# that2180_vca_new.net
KiCad netlist of a schematic drawn in EAGLE
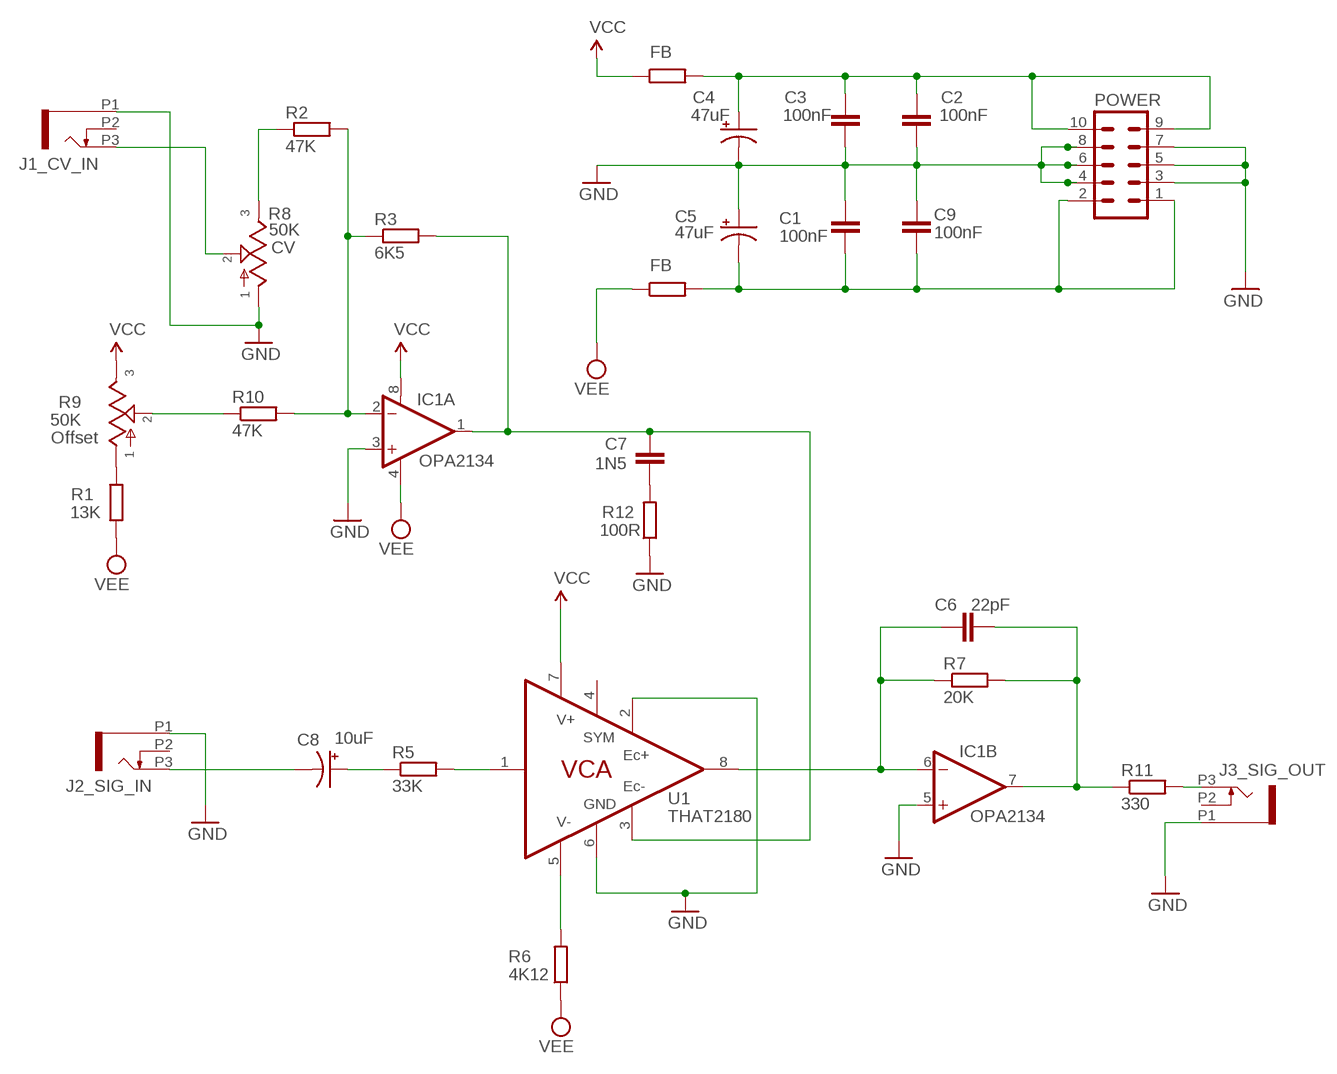
[diagram p0: schematic, sheet 1]

(export (version "E")
  (design (tool "Eeschema 10.0.6"))
  (components
    (comp (ref "C1")
      (value "100nF")
      (footprint "eagle-import:C050-025X075")
      (libsource (lib "eagle-import") (part "C-EU050-025X075"))
    )
    (comp (ref "C2")
      (value "100nF")
      (footprint "eagle-import:C050-025X075")
      (libsource (lib "eagle-import") (part "C-EU050-025X075"))
    )
    (comp (ref "C3")
      (value "100nF")
      (footprint "eagle-import:C050-025X075")
      (libsource (lib "eagle-import") (part "C-EU050-025X075"))
    )
    (comp (ref "C4")
      (value "47uF")
      (footprint "eagle-import:E2,5-5")
      (libsource (lib "eagle-import") (part "CPOL-USE2.5-5"))
    )
    (comp (ref "C5")
      (value "47uF")
      (footprint "eagle-import:E2,5-5")
      (libsource (lib "eagle-import") (part "CPOL-USE2.5-5"))
    )
    (comp (ref "C6")
      (value "22pF")
      (footprint "eagle-import:C050-025X075")
      (libsource (lib "eagle-import") (part "C-EU050-025X075"))
    )
    (comp (ref "C7")
      (value "1N5")
      (footprint "eagle-import:C050-025X075")
      (libsource (lib "eagle-import") (part "C-EU050-025X075"))
    )
    (comp (ref "C8")
      (value "10uF")
      (footprint "eagle-import:E2,5-5")
      (libsource (lib "eagle-import") (part "CPOL-USE2.5-5"))
    )
    (comp (ref "C9")
      (value "100nF")
      (footprint "eagle-import:C050-025X075")
      (libsource (lib "eagle-import") (part "C-EU050-025X075"))
    )
    (comp (ref "IC1")
      (value "OPAMP-DUALDIP")
      (footprint "eagle-import:DIP08")
      (libsource (lib "eagle-import") (part "OPAMP-DUALDIP"))
    )
    (comp (ref "J1_CV_IN")
      (value "PJ301_THONKICONN6")
      (footprint "eagle-import:WQP_PJ_301M6")
      (libsource (lib "eagle-import") (part "PJ301_THONKICONN6"))
    )
    (comp (ref "J2_SIG_IN")
      (value "PJ301_THONKICONN6")
      (footprint "eagle-import:WQP_PJ_301M6")
      (libsource (lib "eagle-import") (part "PJ301_THONKICONN6"))
    )
    (comp (ref "J3_SIG_OUT")
      (value "PJ301_THONKICONN6")
      (footprint "eagle-import:WQP_PJ_301M6")
      (libsource (lib "eagle-import") (part "PJ301_THONKICONN6"))
    )
    (comp (ref "POWER")
      (value "ML10")
      (footprint "eagle-import:ML10")
      (fields (field (name "OC_FARNELL") "unknown") (field (name "OC_NEWARK") "unknown"))
      (libsource (lib "eagle-import") (part "ML10"))
    )
    (comp (ref "R1")
      (value "13K")
      (footprint "eagle-import:0207_10")
      (libsource (lib "eagle-import") (part "R-EU_0207/10"))
    )
    (comp (ref "R2")
      (value "47K")
      (footprint "eagle-import:0207_10")
      (libsource (lib "eagle-import") (part "R-EU_0207/10"))
    )
    (comp (ref "R3")
      (value "6K5")
      (footprint "eagle-import:0207_10")
      (libsource (lib "eagle-import") (part "R-EU_0207/10"))
    )
    (comp (ref "R4")
      (value "FB")
      (footprint "eagle-import:0207_10")
      (libsource (lib "eagle-import") (part "R-EU_0207/10"))
    )
    (comp (ref "R5")
      (value "33K")
      (footprint "eagle-import:0207_10")
      (libsource (lib "eagle-import") (part "R-EU_0207/10"))
    )
    (comp (ref "R6")
      (value "4K12")
      (footprint "eagle-import:0207_10")
      (libsource (lib "eagle-import") (part "R-EU_0207/10"))
    )
    (comp (ref "R7")
      (value "20K")
      (footprint "eagle-import:0207_10")
      (libsource (lib "eagle-import") (part "R-EU_0207/10"))
    )
    (comp (ref "R8")
      (value "50K")
      (footprint "eagle-import:16MM-PCB-MOUNT")
      (libsource (lib "eagle-import") (part "POTPOT"))
    )
    (comp (ref "R9")
      (value "50K")
      (footprint "eagle-import:16MM-PCB-MOUNT")
      (libsource (lib "eagle-import") (part "POTPOT"))
    )
    (comp (ref "R10")
      (value "47K")
      (footprint "eagle-import:0207_10")
      (libsource (lib "eagle-import") (part "R-EU_0207/10"))
    )
    (comp (ref "R11")
      (value "330")
      (footprint "eagle-import:0207_10")
      (libsource (lib "eagle-import") (part "R-EU_0207/10"))
    )
    (comp (ref "R12")
      (value "100R")
      (footprint "eagle-import:0207_10")
      (libsource (lib "eagle-import") (part "R-EU_0207/10"))
    )
    (comp (ref "R13")
      (value "FB")
      (footprint "eagle-import:0207_10")
      (libsource (lib "eagle-import") (part "R-EU_0207/10"))
    )
    (comp (ref "U1")
      (value "THAT2180")
      (footprint "eagle-import:SIP8")
      (libsource (lib "eagle-import") (part "THAT2180"))
    )
  )
  (nets
    (net (code "1") (name "GND") (class "Default")
      (node (ref "C1") (pin "2") (pinfunction "2_2") (pintype "passive"))
      (node (ref "C2") (pin "1") (pinfunction "1_1") (pintype "passive"))
      (node (ref "C3") (pin "1") (pinfunction "1_1") (pintype "passive"))
      (node (ref "C4") (pin "-") (pinfunction "-_-") (pintype "passive"))
      (node (ref "C5") (pin "+") (pinfunction "+_+") (pintype "passive"))
      (node (ref "C9") (pin "2") (pinfunction "2_2") (pintype "passive"))
      (node (ref "IC1") (pin "3") (pinfunction "+IN_3") (pintype "input"))
      (node (ref "IC1") (pin "5") (pinfunction "+IN_5") (pintype "input"))
      (node (ref "J1_CV_IN") (pin "P1") (pinfunction "1_P1") (pintype "passive"))
      (node (ref "J2_SIG_IN") (pin "P1") (pinfunction "1_P1") (pintype "passive"))
      (node (ref "J3_SIG_OUT") (pin "P1") (pinfunction "1_P1") (pintype "passive"))
      (node (ref "POWER") (pin "3") (pinfunction "3_3") (pintype "passive"))
      (node (ref "POWER") (pin "4") (pinfunction "4_4") (pintype "passive"))
      (node (ref "POWER") (pin "5") (pinfunction "5_5") (pintype "passive"))
      (node (ref "POWER") (pin "6") (pinfunction "6_6") (pintype "passive"))
      (node (ref "POWER") (pin "7") (pinfunction "7_7") (pintype "passive"))
      (node (ref "POWER") (pin "8") (pinfunction "8_8") (pintype "passive"))
      (node (ref "R12") (pin "1") (pinfunction "1_1") (pintype "passive"))
      (node (ref "R8") (pin "1") (pinfunction "1_1") (pintype "passive"))
      (node (ref "U1") (pin "2") (pinfunction "EC+_2") (pintype "passive"))
      (node (ref "U1") (pin "6") (pinfunction "GND_6") (pintype "passive"))
    )
    (net (code "2") (name "Net-(C7-Pad1)") (class "Default")
      (node (ref "C7") (pin "1") (pinfunction "1_1") (pintype "passive"))
      (node (ref "R12") (pin "2") (pinfunction "2_2") (pintype "passive"))
    )
    (net (code "3") (name "Net-(C8-Pad+)") (class "Default")
      (node (ref "C8") (pin "+") (pinfunction "+_+") (pintype "passive"))
      (node (ref "R5") (pin "1") (pinfunction "1_1") (pintype "passive"))
    )
    (net (code "4") (name "Net-(IC1A--IN)") (class "Default")
      (node (ref "IC1") (pin "2") (pinfunction "-IN_2") (pintype "input"))
      (node (ref "R10") (pin "2") (pinfunction "2_2") (pintype "passive"))
      (node (ref "R2") (pin "2") (pinfunction "2_2") (pintype "passive"))
      (node (ref "R3") (pin "1") (pinfunction "1_1") (pintype "passive"))
    )
    (net (code "5") (name "Net-(IC1A-OUT)") (class "Default")
      (node (ref "C7") (pin "2") (pinfunction "2_2") (pintype "passive"))
      (node (ref "IC1") (pin "1") (pinfunction "OUT_1") (pintype "output"))
      (node (ref "R3") (pin "2") (pinfunction "2_2") (pintype "passive"))
      (node (ref "U1") (pin "3") (pinfunction "EC-_3") (pintype "output"))
    )
    (net (code "6") (name "Net-(IC1B--IN)") (class "Default")
      (node (ref "C6") (pin "1") (pinfunction "1_1") (pintype "passive"))
      (node (ref "IC1") (pin "6") (pinfunction "-IN_6") (pintype "input"))
      (node (ref "R7") (pin "1") (pinfunction "1_1") (pintype "passive"))
      (node (ref "U1") (pin "8") (pinfunction "OUT_8") (pintype "output"))
    )
    (net (code "7") (name "Net-(IC1B-OUT)") (class "Default")
      (node (ref "C6") (pin "2") (pinfunction "2_2") (pintype "passive"))
      (node (ref "IC1") (pin "7") (pinfunction "OUT_7") (pintype "output"))
      (node (ref "R11") (pin "1") (pinfunction "1_1") (pintype "passive"))
      (node (ref "R7") (pin "2") (pinfunction "2_2") (pintype "passive"))
    )
    (net (code "8") (name "Net-(J1_CV_IN-3)") (class "Default")
      (node (ref "J1_CV_IN") (pin "P3") (pinfunction "3_P3") (pintype "passive"))
      (node (ref "R8") (pin "2") (pinfunction "2_2") (pintype "passive"))
    )
    (net (code "9") (name "Net-(J2_SIG_IN-3)") (class "Default")
      (node (ref "C8") (pin "-") (pinfunction "-_-") (pintype "passive"))
      (node (ref "J2_SIG_IN") (pin "P3") (pinfunction "3_P3") (pintype "passive"))
    )
    (net (code "10") (name "Net-(J3_SIG_OUT-3)") (class "Default")
      (node (ref "J3_SIG_OUT") (pin "P3") (pinfunction "3_P3") (pintype "passive"))
      (node (ref "R11") (pin "2") (pinfunction "2_2") (pintype "passive"))
    )
    (net (code "11") (name "Net-(R1-Pad2)") (class "Default")
      (node (ref "R1") (pin "2") (pinfunction "2_2") (pintype "passive"))
      (node (ref "R9") (pin "1") (pinfunction "1_1") (pintype "passive"))
    )
    (net (code "12") (name "Net-(R2-Pad1)") (class "Default")
      (node (ref "R2") (pin "1") (pinfunction "1_1") (pintype "passive"))
      (node (ref "R8") (pin "3") (pinfunction "3_3") (pintype "passive"))
    )
    (net (code "13") (name "Net-(R10-Pad1)") (class "Default")
      (node (ref "R10") (pin "1") (pinfunction "1_1") (pintype "passive"))
      (node (ref "R9") (pin "2") (pinfunction "2_2") (pintype "passive"))
    )
    (net (code "14") (name "Net-(U1-IN)") (class "Default")
      (node (ref "R5") (pin "2") (pinfunction "2_2") (pintype "passive"))
      (node (ref "U1") (pin "1") (pinfunction "IN_1") (pintype "input"))
    )
    (net (code "15") (name "Net-(U1-V-)") (class "Default")
      (node (ref "R6") (pin "2") (pinfunction "2_2") (pintype "passive"))
      (node (ref "U1") (pin "5") (pinfunction "V-_5") (pintype "power_in"))
    )
    (net (code "16") (name "VCC") (class "Default")
      (node (ref "C2") (pin "2") (pinfunction "2_2") (pintype "passive"))
      (node (ref "C3") (pin "2") (pinfunction "2_2") (pintype "passive"))
      (node (ref "C4") (pin "+") (pinfunction "+_+") (pintype "passive"))
      (node (ref "IC1") (pin "8") (pinfunction "V+_8") (pintype "power_in"))
      (node (ref "POWER") (pin "10") (pinfunction "10_10") (pintype "passive"))
      (node (ref "POWER") (pin "9") (pinfunction "9_9") (pintype "passive"))
      (node (ref "R4") (pin "1") (pinfunction "1_1") (pintype "passive"))
      (node (ref "R4") (pin "2") (pinfunction "2_2") (pintype "passive"))
      (node (ref "R9") (pin "3") (pinfunction "3_3") (pintype "passive"))
      (node (ref "U1") (pin "7") (pinfunction "V+_7") (pintype "power_in"))
    )
    (net (code "17") (name "VEE") (class "Default")
      (node (ref "C1") (pin "1") (pinfunction "1_1") (pintype "passive"))
      (node (ref "C5") (pin "-") (pinfunction "-_-") (pintype "passive"))
      (node (ref "C9") (pin "1") (pinfunction "1_1") (pintype "passive"))
      (node (ref "IC1") (pin "4") (pinfunction "V-_4") (pintype "power_in"))
      (node (ref "POWER") (pin "1") (pinfunction "1_1") (pintype "passive"))
      (node (ref "POWER") (pin "2") (pinfunction "2_2") (pintype "passive"))
      (node (ref "R1") (pin "1") (pinfunction "1_1") (pintype "passive"))
      (node (ref "R13") (pin "1") (pinfunction "1_1") (pintype "passive"))
      (node (ref "R13") (pin "2") (pinfunction "2_2") (pintype "passive"))
      (node (ref "R6") (pin "1") (pinfunction "1_1") (pintype "passive"))
    )
    (net (code "18") (name "unconnected-(J1_CV_IN-2-PadP2)") (class "Default")
      (node (ref "J1_CV_IN") (pin "P2") (pinfunction "2_P2") (pintype "passive"))
    )
    (net (code "19") (name "unconnected-(J2_SIG_IN-2-PadP2)") (class "Default")
      (node (ref "J2_SIG_IN") (pin "P2") (pinfunction "2_P2") (pintype "passive"))
    )
    (net (code "20") (name "unconnected-(J3_SIG_OUT-2-PadP2)") (class "Default")
      (node (ref "J3_SIG_OUT") (pin "P2") (pinfunction "2_P2") (pintype "passive"))
    )
    (net (code "21") (name "unconnected-(U1-SYM-Pad4)") (class "Default")
      (node (ref "U1") (pin "4") (pinfunction "SYM_4") (pintype "passive"))
    )
  )
)
